# DueShieldTopOnly.net
KiCad netlist of a schematic drawn in EAGLE
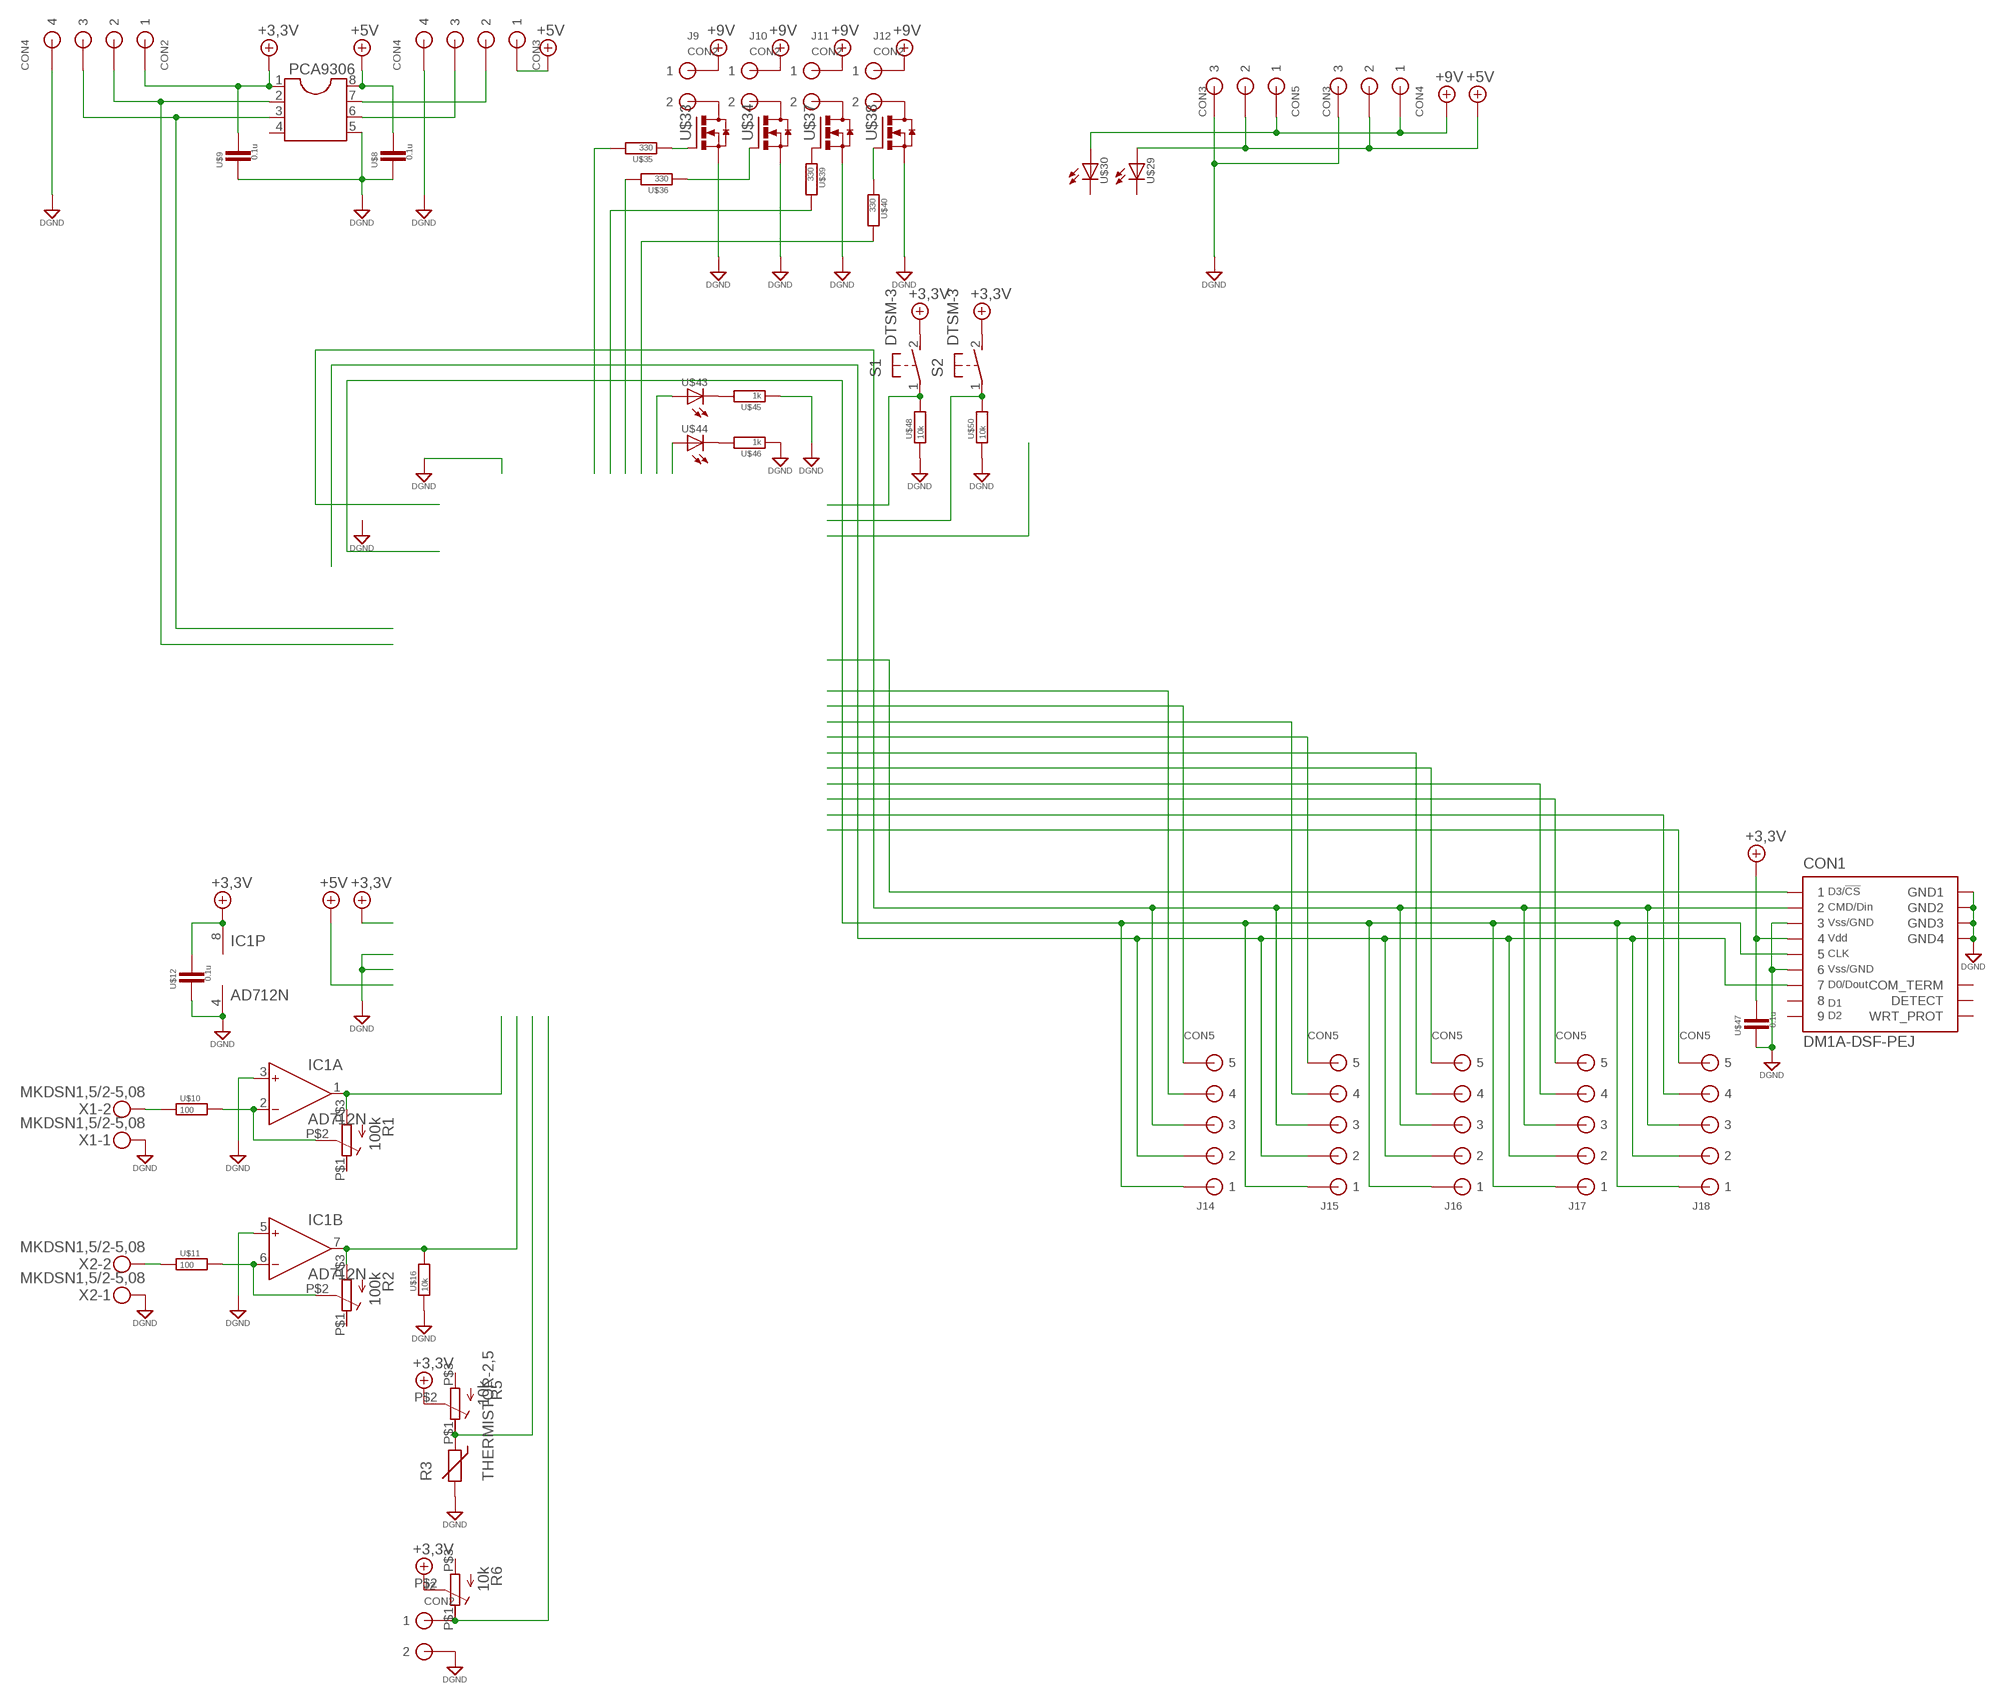
[diagram p0: schematic, sheet 1]

(export (version "E")
  (design (tool "Eeschema 10.0.6"))
  (components
    (comp (ref "CON1")
      (value "DM1A-DSF-PEJ")
      (footprint "eagle-import:DM1A-DSF-PEJ")
      (libsource (lib "eagle-import") (part "DM1A-DSF-PEJ"))
    )
    (comp (ref "CON2")
      (value "CON4")
      (footprint "eagle-import:CON4")
      (libsource (lib "eagle-import") (part "CON4"))
    )
    (comp (ref "CON3")
      (value "CON4")
      (footprint "eagle-import:CON4")
      (libsource (lib "eagle-import") (part "CON4"))
    )
    (comp (ref "CON4")
      (value "CON3")
      (footprint "eagle-import:CON3")
      (libsource (lib "eagle-import") (part "CON3"))
    )
    (comp (ref "CON5")
      (value "CON3")
      (footprint "eagle-import:CON3")
      (libsource (lib "eagle-import") (part "CON3"))
    )
    (comp (ref "IC1")
      (value "AD712N")
      (footprint "eagle-import:DIL08")
      (fields (field (name "MF") "ALTERA CORPORATION") (field (name "MPN") "AD712JNZ"))
      (libsource (lib "eagle-import") (part "AD712N"))
    )
    (comp (ref "J2")
      (value "CON2")
      (footprint "eagle-import:CON2")
      (libsource (lib "eagle-import") (part "CON2"))
    )
    (comp (ref "J9")
      (value "CON2")
      (footprint "eagle-import:CON2")
      (libsource (lib "eagle-import") (part "CON2"))
    )
    (comp (ref "J10")
      (value "CON2")
      (footprint "eagle-import:CON2")
      (libsource (lib "eagle-import") (part "CON2"))
    )
    (comp (ref "J11")
      (value "CON2")
      (footprint "eagle-import:CON2")
      (libsource (lib "eagle-import") (part "CON2"))
    )
    (comp (ref "J12")
      (value "CON2")
      (footprint "eagle-import:CON2")
      (libsource (lib "eagle-import") (part "CON2"))
    )
    (comp (ref "J14")
      (value "CON5")
      (footprint "eagle-import:CON5")
      (libsource (lib "eagle-import") (part "CON5"))
    )
    (comp (ref "J15")
      (value "CON5")
      (footprint "eagle-import:CON5")
      (libsource (lib "eagle-import") (part "CON5"))
    )
    (comp (ref "J16")
      (value "CON5")
      (footprint "eagle-import:CON5")
      (libsource (lib "eagle-import") (part "CON5"))
    )
    (comp (ref "J17")
      (value "CON5")
      (footprint "eagle-import:CON5")
      (libsource (lib "eagle-import") (part "CON5"))
    )
    (comp (ref "J18")
      (value "CON5")
      (footprint "eagle-import:CON5")
      (libsource (lib "eagle-import") (part "CON5"))
    )
    (comp (ref "PCA9306")
      (value "DIL8")
      (footprint "eagle-import:DIL08")
      (libsource (lib "eagle-import") (part "DIL8"))
    )
    (comp (ref "R1")
      (value "100k")
      (footprint "eagle-import:GF063PB")
      (libsource (lib "eagle-import") (part "抵抗(可変)"))
    )
    (comp (ref "R2")
      (value "100k")
      (footprint "eagle-import:GF063PB")
      (libsource (lib "eagle-import") (part "抵抗(可変)"))
    )
    (comp (ref "R3")
      (value "THERMISTOR-2,5")
      (footprint "eagle-import:RS-2,5")
      (libsource (lib "eagle-import") (part "THERMISTOR-2,5"))
    )
    (comp (ref "R5")
      (value "10k")
      (footprint "eagle-import:GF063PB")
      (libsource (lib "eagle-import") (part "抵抗(可変)"))
    )
    (comp (ref "R6")
      (value "10k")
      (footprint "eagle-import:GF063PB")
      (libsource (lib "eagle-import") (part "抵抗(可変)"))
    )
    (comp (ref "S1")
      (value "DTSM-3")
      (footprint "eagle-import:DTSM-3")
      (libsource (lib "eagle-import") (part "DTSM-3"))
    )
    (comp (ref "S2")
      (value "DTSM-3")
      (footprint "eagle-import:DTSM-3")
      (libsource (lib "eagle-import") (part "DTSM-3"))
    )
    (comp (ref "U$8")
      (value "0.1u")
      (footprint "eagle-import:0805")
      (libsource (lib "eagle-import") (part "コンデンサ0805"))
    )
    (comp (ref "U$9")
      (value "0.1u")
      (footprint "eagle-import:0805")
      (libsource (lib "eagle-import") (part "コンデンサ0805"))
    )
    (comp (ref "U$10")
      (value "100")
      (footprint "eagle-import:0805")
      (libsource (lib "eagle-import") (part "抵抗0805"))
    )
    (comp (ref "U$11")
      (value "100")
      (footprint "eagle-import:0805")
      (libsource (lib "eagle-import") (part "抵抗0805"))
    )
    (comp (ref "U$12")
      (value "0.1u")
      (footprint "eagle-import:0805")
      (libsource (lib "eagle-import") (part "コンデンサ0805"))
    )
    (comp (ref "U$16")
      (value "10k")
      (footprint "eagle-import:0805")
      (libsource (lib "eagle-import") (part "抵抗0805"))
    )
    (comp (ref "U$29")
      (value "LED(砲弾型)3")
      (footprint "eagle-import:LED3MM")
      (libsource (lib "eagle-import") (part "LED(砲弾型)3"))
    )
    (comp (ref "U$30")
      (value "LED(砲弾型)3")
      (footprint "eagle-import:LED3MM")
      (libsource (lib "eagle-import") (part "LED(砲弾型)3"))
    )
    (comp (ref "U$33")
      (value "TO-252(MOS-FET_N)")
      (footprint "eagle-import:TO-252")
      (libsource (lib "eagle-import") (part "TO-252(MOS-FET_N)"))
    )
    (comp (ref "U$34")
      (value "TO-252(MOS-FET_N)")
      (footprint "eagle-import:TO-252")
      (libsource (lib "eagle-import") (part "TO-252(MOS-FET_N)"))
    )
    (comp (ref "U$35")
      (value "330")
      (footprint "eagle-import:0805")
      (libsource (lib "eagle-import") (part "抵抗0805"))
    )
    (comp (ref "U$36")
      (value "330")
      (footprint "eagle-import:0805")
      (libsource (lib "eagle-import") (part "抵抗0805"))
    )
    (comp (ref "U$37")
      (value "TO-252(MOS-FET_N)")
      (footprint "eagle-import:TO-252")
      (libsource (lib "eagle-import") (part "TO-252(MOS-FET_N)"))
    )
    (comp (ref "U$38")
      (value "TO-252(MOS-FET_N)")
      (footprint "eagle-import:TO-252")
      (libsource (lib "eagle-import") (part "TO-252(MOS-FET_N)"))
    )
    (comp (ref "U$39")
      (value "330")
      (footprint "eagle-import:0805")
      (libsource (lib "eagle-import") (part "抵抗0805"))
    )
    (comp (ref "U$40")
      (value "330")
      (footprint "eagle-import:0805")
      (libsource (lib "eagle-import") (part "抵抗0805"))
    )
    (comp (ref "U$43")
      (value "LED(砲弾型)3")
      (footprint "eagle-import:LED3MM")
      (libsource (lib "eagle-import") (part "LED(砲弾型)3"))
    )
    (comp (ref "U$44")
      (value "LED(砲弾型)3")
      (footprint "eagle-import:LED3MM")
      (libsource (lib "eagle-import") (part "LED(砲弾型)3"))
    )
    (comp (ref "U$45")
      (value "1k")
      (footprint "eagle-import:0805")
      (libsource (lib "eagle-import") (part "抵抗0805"))
    )
    (comp (ref "U$46")
      (value "1k")
      (footprint "eagle-import:0805")
      (libsource (lib "eagle-import") (part "抵抗0805"))
    )
    (comp (ref "U$47")
      (value "0.1u")
      (footprint "eagle-import:0805")
      (libsource (lib "eagle-import") (part "コンデンサ0805"))
    )
    (comp (ref "U$48")
      (value "10k")
      (footprint "eagle-import:0805")
      (libsource (lib "eagle-import") (part "抵抗0805"))
    )
    (comp (ref "U$50")
      (value "10k")
      (footprint "eagle-import:0805")
      (libsource (lib "eagle-import") (part "抵抗0805"))
    )
    (comp (ref "X1")
      (value "MKDSN1,5/2-5,08")
      (footprint "eagle-import:MKDSN1,5_2-5,08")
      (libsource (lib "eagle-import") (part "MKDSN1,5/2-5,08"))
    )
    (comp (ref "X2")
      (value "MKDSN1,5/2-5,08")
      (footprint "eagle-import:MKDSN1,5_2-5,08")
      (libsource (lib "eagle-import") (part "MKDSN1,5/2-5,08"))
    )
  )
  (nets
    (net (code "1") (name "+3,3V") (class "Default")
      (node (ref "CON1") (pin "4") (pinfunction "4_4") (pintype "power_in"))
      (node (ref "CON2") (pin "P$1") (pinfunction "1_P$1") (pintype "bidirectional"))
      (node (ref "IC1") (pin "8") (pinfunction "V+_8") (pintype "power_in"))
      (node (ref "PCA9306") (pin "1") (pinfunction "1_1") (pintype "passive"))
      (node (ref "R5") (pin "P$2") (pinfunction "S_P$2") (pintype "passive"))
      (node (ref "R6") (pin "P$2") (pinfunction "S_P$2") (pintype "passive"))
      (node (ref "S1") (pin "2") (pinfunction "2_2") (pintype "passive"))
      (node (ref "S2") (pin "2") (pinfunction "2_2") (pintype "passive"))
      (node (ref "U$12") (pin "1") (pinfunction "1_1") (pintype "passive"))
      (node (ref "U$47") (pin "1") (pinfunction "1_1") (pintype "passive"))
      (node (ref "U$9") (pin "1") (pinfunction "1_1") (pintype "passive"))
    )
    (net (code "2") (name "+5V") (class "Default")
      (node (ref "CON3") (pin "P$1") (pinfunction "1_P$1") (pintype "bidirectional"))
      (node (ref "CON4") (pin "P$2") (pinfunction "2_P$2") (pintype "bidirectional"))
      (node (ref "CON5") (pin "P$2") (pinfunction "2_P$2") (pintype "bidirectional"))
      (node (ref "PCA9306") (pin "8") (pinfunction "8_8") (pintype "passive"))
      (node (ref "U$29") (pin "A") (pinfunction "A_A") (pintype "passive"))
      (node (ref "U$8") (pin "1") (pinfunction "1_1") (pintype "passive"))
    )
    (net (code "3") (name "+9V") (class "Default")
      (node (ref "CON4") (pin "P$1") (pinfunction "1_P$1") (pintype "bidirectional"))
      (node (ref "CON5") (pin "P$1") (pinfunction "1_P$1") (pintype "bidirectional"))
      (node (ref "J10") (pin "P$1") (pinfunction "1_P$1") (pintype "bidirectional"))
      (node (ref "J11") (pin "P$1") (pinfunction "1_P$1") (pintype "bidirectional"))
      (node (ref "J12") (pin "P$1") (pinfunction "1_P$1") (pintype "bidirectional"))
      (node (ref "J9") (pin "P$1") (pinfunction "1_P$1") (pintype "bidirectional"))
      (node (ref "U$30") (pin "A") (pinfunction "A_A") (pintype "passive"))
    )
    (net (code "4") (name "DGND") (class "Default")
      (node (ref "CON1") (pin "3") (pinfunction "3_3") (pintype "power_in"))
      (node (ref "CON1") (pin "6") (pinfunction "6_6") (pintype "power_in"))
      (node (ref "CON1") (pin "GND1") (pinfunction "GND1_GND1") (pintype "power_in"))
      (node (ref "CON1") (pin "GND2") (pinfunction "GND2_GND2") (pintype "power_in"))
      (node (ref "CON1") (pin "GND3") (pinfunction "GND3_GND3") (pintype "power_in"))
      (node (ref "CON1") (pin "GND4") (pinfunction "GND4_GND4") (pintype "power_in"))
      (node (ref "CON2") (pin "P$4") (pinfunction "4_P$4") (pintype "bidirectional"))
      (node (ref "CON3") (pin "P$4") (pinfunction "4_P$4") (pintype "bidirectional"))
      (node (ref "CON4") (pin "P$3") (pinfunction "3_P$3") (pintype "bidirectional"))
      (node (ref "CON5") (pin "P$3") (pinfunction "3_P$3") (pintype "bidirectional"))
      (node (ref "IC1") (pin "3") (pinfunction "IN+_3") (pintype "input"))
      (node (ref "IC1") (pin "4") (pinfunction "V-_4") (pintype "power_in"))
      (node (ref "IC1") (pin "5") (pinfunction "IN+_5") (pintype "input"))
      (node (ref "J2") (pin "P$2") (pinfunction "2_P$2") (pintype "bidirectional"))
      (node (ref "PCA9306") (pin "5") (pinfunction "5_5") (pintype "passive"))
      (node (ref "R3") (pin "2") (pinfunction "2_2") (pintype "passive"))
      (node (ref "U$12") (pin "2") (pinfunction "2_2") (pintype "passive"))
      (node (ref "U$16") (pin "1") (pinfunction "1_1") (pintype "passive"))
      (node (ref "U$33") (pin "2") (pinfunction "S_2") (pintype "passive"))
      (node (ref "U$34") (pin "2") (pinfunction "S_2") (pintype "passive"))
      (node (ref "U$37") (pin "2") (pinfunction "S_2") (pintype "passive"))
      (node (ref "U$38") (pin "2") (pinfunction "S_2") (pintype "passive"))
      (node (ref "U$45") (pin "1") (pinfunction "1_1") (pintype "passive"))
      (node (ref "U$46") (pin "1") (pinfunction "1_1") (pintype "passive"))
      (node (ref "U$47") (pin "2") (pinfunction "2_2") (pintype "passive"))
      (node (ref "U$48") (pin "1") (pinfunction "1_1") (pintype "passive"))
      (node (ref "U$50") (pin "1") (pinfunction "1_1") (pintype "passive"))
      (node (ref "U$8") (pin "2") (pinfunction "2_2") (pintype "passive"))
      (node (ref "U$9") (pin "2") (pinfunction "2_2") (pintype "passive"))
      (node (ref "X1") (pin "1") (pinfunction "KL_1") (pintype "passive"))
      (node (ref "X2") (pin "1") (pinfunction "KL_1") (pintype "passive"))
    )
    (net (code "5") (name "Net-(CON2-2)") (class "Default")
      (node (ref "CON2") (pin "P$2") (pinfunction "2_P$2") (pintype "bidirectional"))
      (node (ref "PCA9306") (pin "2") (pinfunction "2_2") (pintype "passive"))
    )
    (net (code "6") (name "Net-(CON2-3)") (class "Default")
      (node (ref "CON2") (pin "P$3") (pinfunction "3_P$3") (pintype "bidirectional"))
      (node (ref "PCA9306") (pin "3") (pinfunction "3_3") (pintype "passive"))
    )
    (net (code "7") (name "Net-(CON3-2)") (class "Default")
      (node (ref "CON3") (pin "P$2") (pinfunction "2_P$2") (pintype "bidirectional"))
      (node (ref "PCA9306") (pin "7") (pinfunction "7_7") (pintype "passive"))
    )
    (net (code "8") (name "Net-(CON3-3)") (class "Default")
      (node (ref "CON3") (pin "P$3") (pinfunction "3_P$3") (pintype "bidirectional"))
      (node (ref "PCA9306") (pin "6") (pinfunction "6_6") (pintype "passive"))
    )
    (net (code "9") (name "Net-(IC1A-IN-)") (class "Default")
      (node (ref "IC1") (pin "2") (pinfunction "IN-_2") (pintype "input"))
      (node (ref "R1") (pin "P$2") (pinfunction "S_P$2") (pintype "passive"))
      (node (ref "U$10") (pin "2") (pinfunction "2_2") (pintype "passive"))
    )
    (net (code "10") (name "Net-(IC1A-OUT)") (class "Default")
      (node (ref "IC1") (pin "1") (pinfunction "OUT_1") (pintype "output"))
      (node (ref "R1") (pin "P$3") (pinfunction "A_P$3") (pintype "passive"))
    )
    (net (code "11") (name "Net-(IC1B-IN-)") (class "Default")
      (node (ref "IC1") (pin "6") (pinfunction "IN-_6") (pintype "input"))
      (node (ref "R2") (pin "P$2") (pinfunction "S_P$2") (pintype "passive"))
      (node (ref "U$11") (pin "2") (pinfunction "2_2") (pintype "passive"))
    )
    (net (code "12") (name "Net-(IC1B-OUT)") (class "Default")
      (node (ref "IC1") (pin "7") (pinfunction "OUT_7") (pintype "output"))
      (node (ref "R2") (pin "P$3") (pinfunction "A_P$3") (pintype "passive"))
      (node (ref "U$16") (pin "2") (pinfunction "2_2") (pintype "passive"))
    )
    (net (code "13") (name "Net-(J2-1)") (class "Default")
      (node (ref "J2") (pin "P$1") (pinfunction "1_P$1") (pintype "bidirectional"))
      (node (ref "R6") (pin "P$1") (pinfunction "E_P$1") (pintype "passive"))
    )
    (net (code "14") (name "Net-(J9-2)") (class "Default")
      (node (ref "J9") (pin "P$2") (pinfunction "2_P$2") (pintype "bidirectional"))
      (node (ref "U$33") (pin "3") (pinfunction "D_3") (pintype "passive"))
    )
    (net (code "15") (name "Net-(J10-2)") (class "Default")
      (node (ref "J10") (pin "P$2") (pinfunction "2_P$2") (pintype "bidirectional"))
      (node (ref "U$34") (pin "3") (pinfunction "D_3") (pintype "passive"))
    )
    (net (code "16") (name "Net-(J11-2)") (class "Default")
      (node (ref "J11") (pin "P$2") (pinfunction "2_P$2") (pintype "bidirectional"))
      (node (ref "U$37") (pin "3") (pinfunction "D_3") (pintype "passive"))
    )
    (net (code "17") (name "Net-(J12-2)") (class "Default")
      (node (ref "J12") (pin "P$2") (pinfunction "2_P$2") (pintype "bidirectional"))
      (node (ref "U$38") (pin "3") (pinfunction "D_3") (pintype "passive"))
    )
    (net (code "18") (name "Net-(J14-1)") (class "Default")
      (node (ref "CON1") (pin "5") (pinfunction "5_5") (pintype "input"))
      (node (ref "J14") (pin "P$1") (pinfunction "1_P$1") (pintype "bidirectional"))
      (node (ref "J15") (pin "P$1") (pinfunction "1_P$1") (pintype "bidirectional"))
      (node (ref "J16") (pin "P$1") (pinfunction "1_P$1") (pintype "bidirectional"))
      (node (ref "J17") (pin "P$1") (pinfunction "1_P$1") (pintype "bidirectional"))
      (node (ref "J18") (pin "P$1") (pinfunction "1_P$1") (pintype "bidirectional"))
    )
    (net (code "19") (name "Net-(J14-2)") (class "Default")
      (node (ref "CON1") (pin "7") (pinfunction "7_7") (pintype "bidirectional"))
      (node (ref "J14") (pin "P$2") (pinfunction "2_P$2") (pintype "bidirectional"))
      (node (ref "J15") (pin "P$2") (pinfunction "2_P$2") (pintype "bidirectional"))
      (node (ref "J16") (pin "P$2") (pinfunction "2_P$2") (pintype "bidirectional"))
      (node (ref "J17") (pin "P$2") (pinfunction "2_P$2") (pintype "bidirectional"))
      (node (ref "J18") (pin "P$2") (pinfunction "2_P$2") (pintype "bidirectional"))
    )
    (net (code "20") (name "Net-(J14-3)") (class "Default")
      (node (ref "CON1") (pin "2") (pinfunction "2_2") (pintype "input"))
      (node (ref "J14") (pin "P$3") (pinfunction "3_P$3") (pintype "bidirectional"))
      (node (ref "J15") (pin "P$3") (pinfunction "3_P$3") (pintype "bidirectional"))
      (node (ref "J16") (pin "P$3") (pinfunction "3_P$3") (pintype "bidirectional"))
      (node (ref "J17") (pin "P$3") (pinfunction "3_P$3") (pintype "bidirectional"))
      (node (ref "J18") (pin "P$3") (pinfunction "3_P$3") (pintype "bidirectional"))
    )
    (net (code "21") (name "Net-(R5-E)") (class "Default")
      (node (ref "R3") (pin "1") (pinfunction "1_1") (pintype "passive"))
      (node (ref "R5") (pin "P$1") (pinfunction "E_P$1") (pintype "passive"))
    )
    (net (code "22") (name "Net-(S1-Pad1)") (class "Default")
      (node (ref "S1") (pin "1") (pinfunction "1_1") (pintype "passive"))
      (node (ref "U$48") (pin "2") (pinfunction "2_2") (pintype "passive"))
    )
    (net (code "23") (name "Net-(S2-Pad1)") (class "Default")
      (node (ref "S2") (pin "1") (pinfunction "1_1") (pintype "passive"))
      (node (ref "U$50") (pin "2") (pinfunction "2_2") (pintype "passive"))
    )
    (net (code "24") (name "Net-(U$33-G)") (class "Default")
      (node (ref "U$33") (pin "1") (pinfunction "G_1") (pintype "passive"))
      (node (ref "U$35") (pin "1") (pinfunction "1_1") (pintype "passive"))
    )
    (net (code "25") (name "Net-(U$34-G)") (class "Default")
      (node (ref "U$34") (pin "1") (pinfunction "G_1") (pintype "passive"))
      (node (ref "U$36") (pin "1") (pinfunction "1_1") (pintype "passive"))
    )
    (net (code "26") (name "Net-(U$37-G)") (class "Default")
      (node (ref "U$37") (pin "1") (pinfunction "G_1") (pintype "passive"))
      (node (ref "U$39") (pin "1") (pinfunction "1_1") (pintype "passive"))
    )
    (net (code "27") (name "Net-(U$38-G)") (class "Default")
      (node (ref "U$38") (pin "1") (pinfunction "G_1") (pintype "passive"))
      (node (ref "U$40") (pin "1") (pinfunction "1_1") (pintype "passive"))
    )
    (net (code "28") (name "Net-(U$43-PadK)") (class "Default")
      (node (ref "U$43") (pin "K") (pinfunction "K_K") (pintype "passive"))
      (node (ref "U$45") (pin "2") (pinfunction "2_2") (pintype "passive"))
    )
    (net (code "29") (name "Net-(U$44-PadK)") (class "Default")
      (node (ref "U$44") (pin "K") (pinfunction "K_K") (pintype "passive"))
      (node (ref "U$46") (pin "2") (pinfunction "2_2") (pintype "passive"))
    )
    (net (code "30") (name "Net-(X1B-KL)") (class "Default")
      (node (ref "U$10") (pin "1") (pinfunction "1_1") (pintype "passive"))
      (node (ref "X1") (pin "2") (pinfunction "KL_2") (pintype "passive"))
    )
    (net (code "31") (name "Net-(X2B-KL)") (class "Default")
      (node (ref "U$11") (pin "1") (pinfunction "1_1") (pintype "passive"))
      (node (ref "X2") (pin "2") (pinfunction "KL_2") (pintype "passive"))
    )
    (net (code "32") (name "unconnected-(CON1-Pad1)") (class "Default")
      (node (ref "CON1") (pin "1") (pinfunction "1_1") (pintype "bidirectional"))
    )
    (net (code "33") (name "unconnected-(CON1-Pad8)") (class "Default")
      (node (ref "CON1") (pin "8") (pinfunction "8_8") (pintype "bidirectional"))
    )
    (net (code "34") (name "unconnected-(CON1-Pad9)") (class "Default")
      (node (ref "CON1") (pin "9") (pinfunction "9_9") (pintype "bidirectional"))
    )
    (net (code "35") (name "unconnected-(CON1-PadCOM_TERM)") (class "Default")
      (node (ref "CON1") (pin "COM_TERM") (pinfunction "COM_TERM_COM_TERM") (pintype "output"))
    )
    (net (code "36") (name "unconnected-(CON1-PadDETECT)") (class "Default")
      (node (ref "CON1") (pin "DETECT") (pinfunction "DETECT_DETECT") (pintype "output"))
    )
    (net (code "37") (name "unconnected-(CON1-PadWRT_PROT)") (class "Default")
      (node (ref "CON1") (pin "WRT_PROT") (pinfunction "WRT_PROT_WRT_PROT") (pintype "output"))
    )
    (net (code "38") (name "unconnected-(J14-4-PadP$4)") (class "Default")
      (node (ref "J14") (pin "P$4") (pinfunction "4_P$4") (pintype "bidirectional"))
    )
    (net (code "39") (name "unconnected-(J14-5-PadP$5)") (class "Default")
      (node (ref "J14") (pin "P$5") (pinfunction "5_P$5") (pintype "bidirectional"))
    )
    (net (code "40") (name "unconnected-(J15-4-PadP$4)") (class "Default")
      (node (ref "J15") (pin "P$4") (pinfunction "4_P$4") (pintype "bidirectional"))
    )
    (net (code "41") (name "unconnected-(J15-5-PadP$5)") (class "Default")
      (node (ref "J15") (pin "P$5") (pinfunction "5_P$5") (pintype "bidirectional"))
    )
    (net (code "42") (name "unconnected-(J16-4-PadP$4)") (class "Default")
      (node (ref "J16") (pin "P$4") (pinfunction "4_P$4") (pintype "bidirectional"))
    )
    (net (code "43") (name "unconnected-(J16-5-PadP$5)") (class "Default")
      (node (ref "J16") (pin "P$5") (pinfunction "5_P$5") (pintype "bidirectional"))
    )
    (net (code "44") (name "unconnected-(J17-4-PadP$4)") (class "Default")
      (node (ref "J17") (pin "P$4") (pinfunction "4_P$4") (pintype "bidirectional"))
    )
    (net (code "45") (name "unconnected-(J17-5-PadP$5)") (class "Default")
      (node (ref "J17") (pin "P$5") (pinfunction "5_P$5") (pintype "bidirectional"))
    )
    (net (code "46") (name "unconnected-(J18-4-PadP$4)") (class "Default")
      (node (ref "J18") (pin "P$4") (pinfunction "4_P$4") (pintype "bidirectional"))
    )
    (net (code "47") (name "unconnected-(J18-5-PadP$5)") (class "Default")
      (node (ref "J18") (pin "P$5") (pinfunction "5_P$5") (pintype "bidirectional"))
    )
    (net (code "48") (name "unconnected-(PCA9306-Pad4)") (class "Default")
      (node (ref "PCA9306") (pin "4") (pinfunction "4_4") (pintype "passive"))
    )
    (net (code "49") (name "unconnected-(R1-E-PadP$1)") (class "Default")
      (node (ref "R1") (pin "P$1") (pinfunction "E_P$1") (pintype "passive"))
    )
    (net (code "50") (name "unconnected-(R2-E-PadP$1)") (class "Default")
      (node (ref "R2") (pin "P$1") (pinfunction "E_P$1") (pintype "passive"))
    )
    (net (code "51") (name "unconnected-(R5-A-PadP$3)") (class "Default")
      (node (ref "R5") (pin "P$3") (pinfunction "A_P$3") (pintype "passive"))
    )
    (net (code "52") (name "unconnected-(R6-A-PadP$3)") (class "Default")
      (node (ref "R6") (pin "P$3") (pinfunction "A_P$3") (pintype "passive"))
    )
    (net (code "53") (name "unconnected-(U$29-PadK)") (class "Default")
      (node (ref "U$29") (pin "K") (pinfunction "K_K") (pintype "passive"))
    )
    (net (code "54") (name "unconnected-(U$30-PadK)") (class "Default")
      (node (ref "U$30") (pin "K") (pinfunction "K_K") (pintype "passive"))
    )
    (net (code "55") (name "unconnected-(U$35-Pad2)") (class "Default")
      (node (ref "U$35") (pin "2") (pinfunction "2_2") (pintype "passive"))
    )
    (net (code "56") (name "unconnected-(U$36-Pad2)") (class "Default")
      (node (ref "U$36") (pin "2") (pinfunction "2_2") (pintype "passive"))
    )
    (net (code "57") (name "unconnected-(U$39-Pad2)") (class "Default")
      (node (ref "U$39") (pin "2") (pinfunction "2_2") (pintype "passive"))
    )
    (net (code "58") (name "unconnected-(U$40-Pad2)") (class "Default")
      (node (ref "U$40") (pin "2") (pinfunction "2_2") (pintype "passive"))
    )
    (net (code "59") (name "unconnected-(U$43-PadA)") (class "Default")
      (node (ref "U$43") (pin "A") (pinfunction "A_A") (pintype "passive"))
    )
    (net (code "60") (name "unconnected-(U$44-PadA)") (class "Default")
      (node (ref "U$44") (pin "A") (pinfunction "A_A") (pintype "passive"))
    )
  )
)
